# NAND.net
KiCad netlist of a schematic drawn in EAGLE
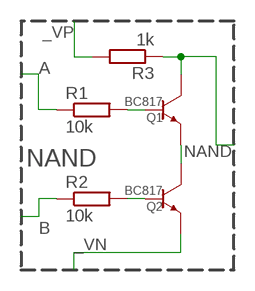
[diagram p0: schematic, sheet 1]

(export (version "E")
  (design (tool "Eeschema 10.0.6"))
  (components
    (comp (ref "Q1")
      (value "BC817")
      (footprint "eagle-import:SOT23")
      (libsource (lib "eagle-import") (part "TRANSISTOR-NPN-GENERIC-SOT23-BECDEFAULT"))
    )
    (comp (ref "Q2")
      (value "BC817")
      (footprint "eagle-import:SOT23")
      (libsource (lib "eagle-import") (part "TRANSISTOR-NPN-GENERIC-SOT23-BECDEFAULT"))
    )
    (comp (ref "R1")
      (value "10k")
      (footprint "eagle-import:R0603")
      (libsource (lib "eagle-import") (part "R-EU_R0603"))
    )
    (comp (ref "R2")
      (value "10k")
      (footprint "eagle-import:R0603")
      (libsource (lib "eagle-import") (part "R-EU_R0603"))
    )
    (comp (ref "R3")
      (value "1k")
      (footprint "eagle-import:R0603")
      (libsource (lib "eagle-import") (part "R-EU_R0603"))
    )
  )
  (nets
    (net (code "1") (name "/A") (class "Default")
      (node (ref "R1") (pin "1") (pinfunction "1_1") (pintype "passive"))
    )
    (net (code "2") (name "/B") (class "Default")
      (node (ref "R2") (pin "1") (pinfunction "1_1") (pintype "passive"))
    )
    (net (code "3") (name "/NAND") (class "Default")
      (node (ref "Q1") (pin "P$3") (pinfunction "COLLECTOR_P$3") (pintype "bidirectional"))
      (node (ref "R3") (pin "1") (pinfunction "1_1") (pintype "passive"))
    )
    (net (code "4") (name "/_VN") (class "Default")
      (node (ref "Q2") (pin "P$2") (pinfunction "EMITTER_P$2") (pintype "bidirectional"))
    )
    (net (code "5") (name "/_VP") (class "Default")
      (node (ref "R3") (pin "2") (pinfunction "2_2") (pintype "passive"))
    )
    (net (code "6") (name "Net-(Q1-BASE)") (class "Default")
      (node (ref "Q1") (pin "P$1") (pinfunction "BASE_P$1") (pintype "bidirectional"))
      (node (ref "R1") (pin "2") (pinfunction "2_2") (pintype "passive"))
    )
    (net (code "7") (name "Net-(Q1-EMITTER)") (class "Default")
      (node (ref "Q1") (pin "P$2") (pinfunction "EMITTER_P$2") (pintype "bidirectional"))
      (node (ref "Q2") (pin "P$3") (pinfunction "COLLECTOR_P$3") (pintype "bidirectional"))
    )
    (net (code "8") (name "Net-(Q2-BASE)") (class "Default")
      (node (ref "Q2") (pin "P$1") (pinfunction "BASE_P$1") (pintype "bidirectional"))
      (node (ref "R2") (pin "2") (pinfunction "2_2") (pintype "passive"))
    )
  )
)
